# Control.net
KiCad netlist of a schematic drawn in Altium Designer
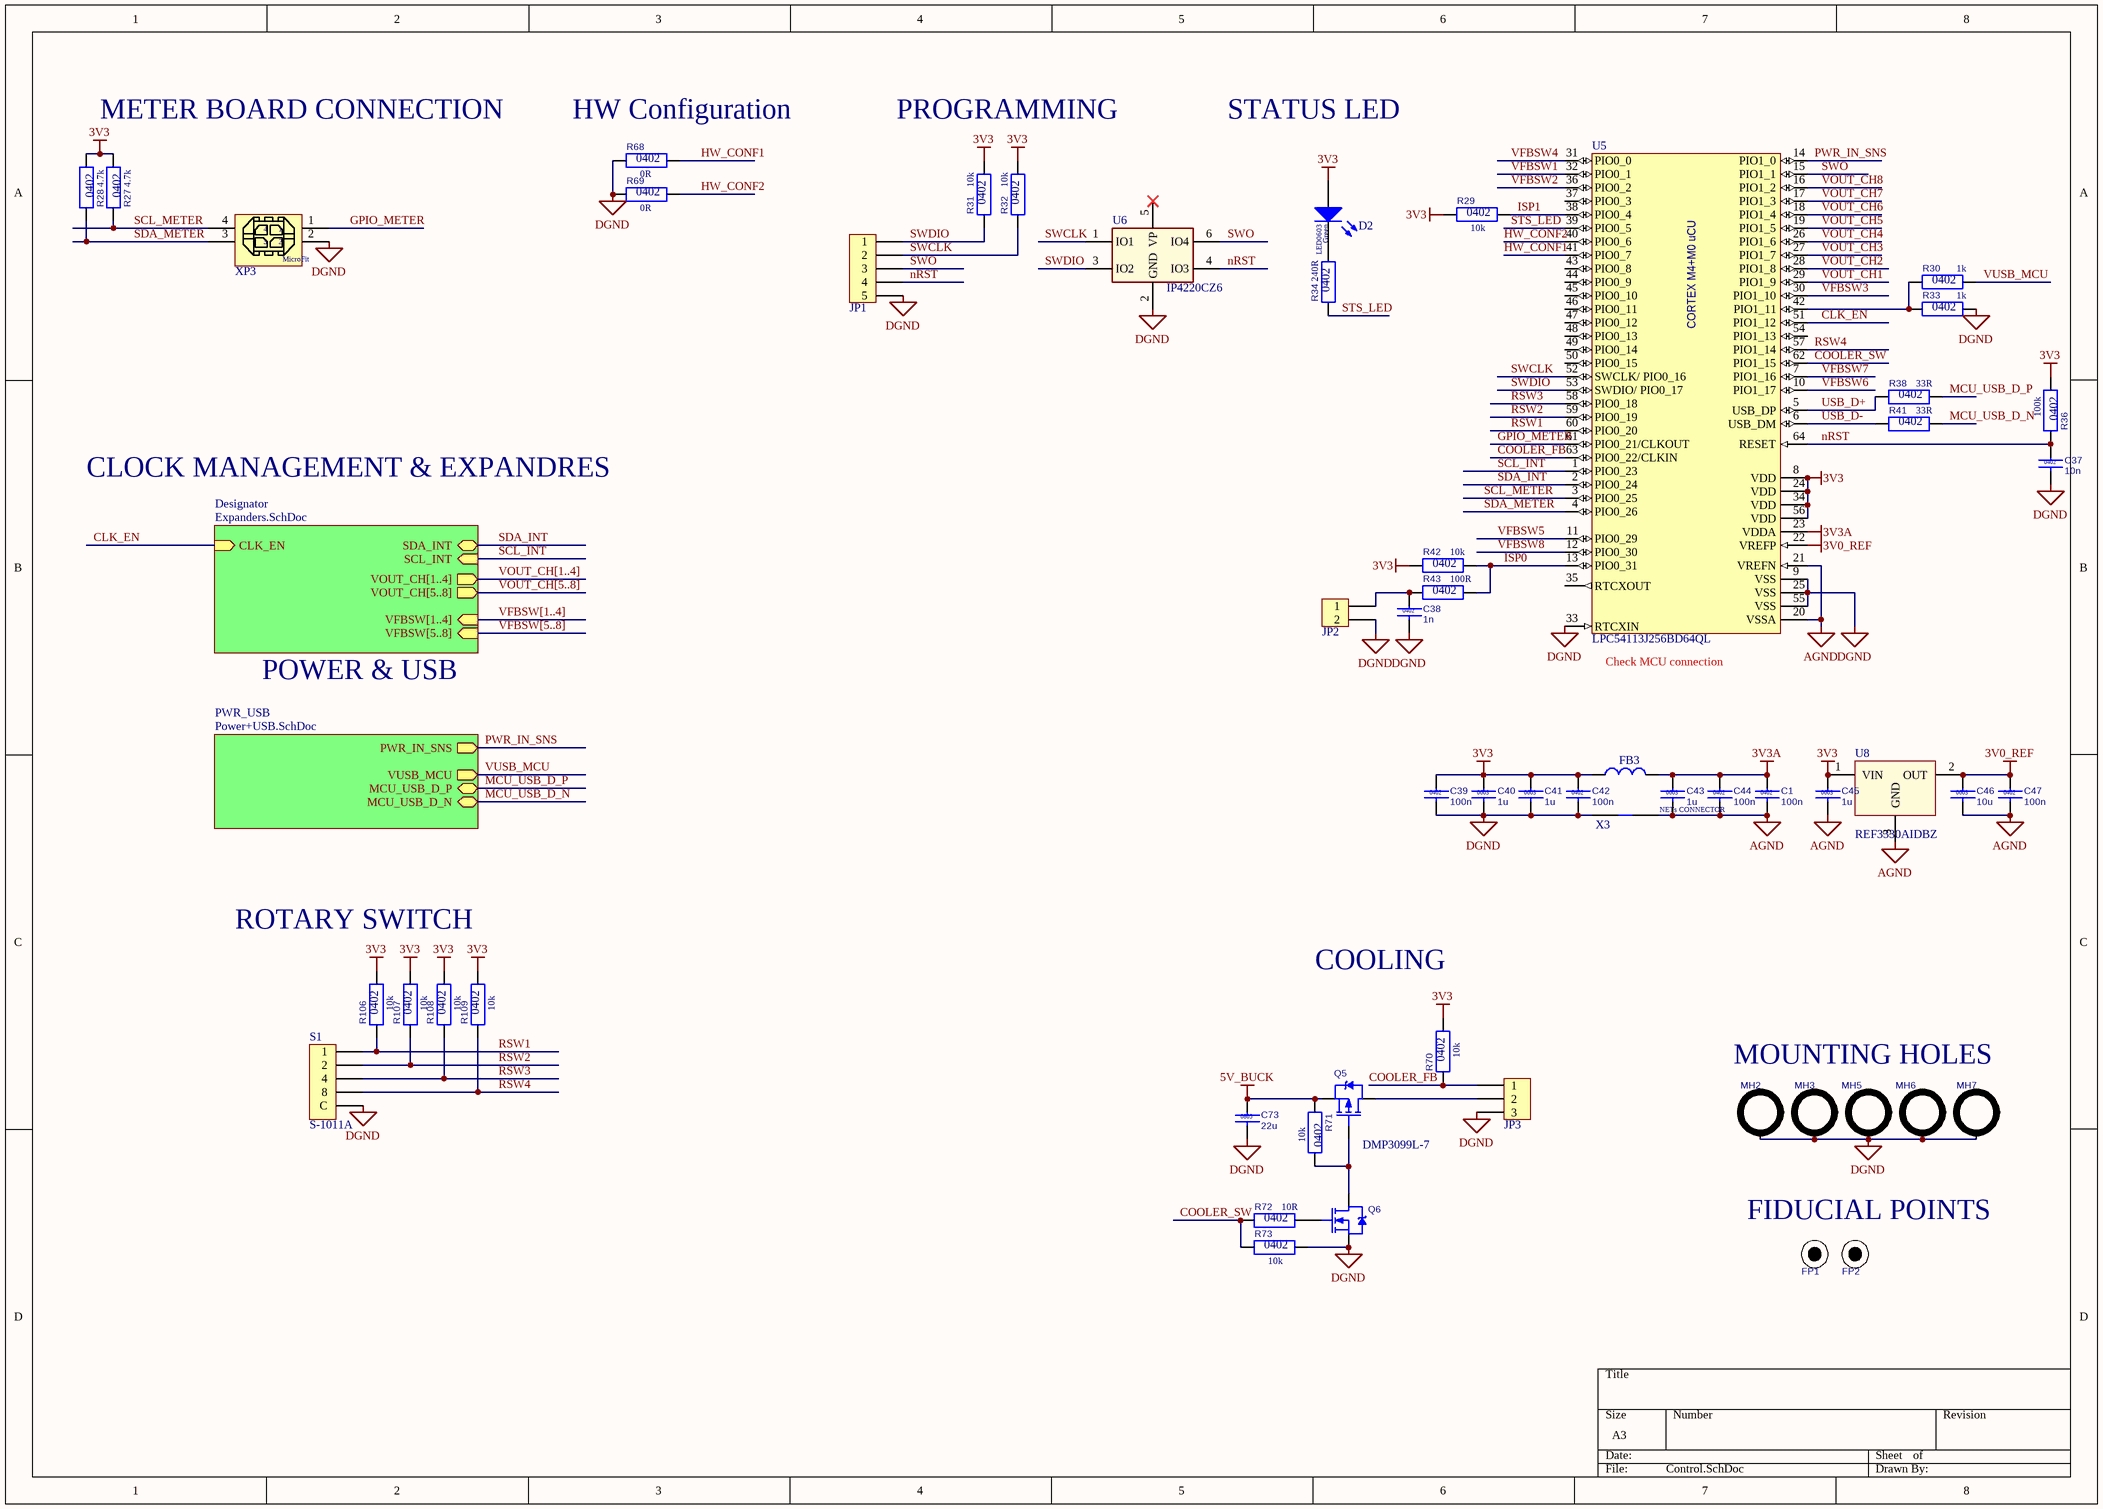
[diagram p0: Control.SchDoc]

(export (version "E")
  (design (tool "Eeschema 10.0.6"))
  (components
    (comp (ref "C1")
      (value "100n")
      (footprint "CC0402M")
      (description "Chip ceramic capacitor")
      (fields
        (field (name "CASE") "0402")
        (field (name "PARTNUMBER") "CC0402K-X7R-25V-100N-M")
        (field (name "MANUFACTURER") "Murata")
        (field (name "PUBLISHER") "alexey.savchenko")
      )
      (libsource (lib "AltiumLib") (part "Capacitor_nonpolar"))
    )
    (comp (ref "C37")
      (value "10n")
      (footprint "CC0402M")
      (description "Chip ceramic capacitor")
      (fields
        (field (name "CASE") "0402")
        (field (name "PARTNUMBER") "CC0402K-X7R-50V-10N-M")
        (field (name "MANUFACTURER") "Yageo")
        (field (name "PUBLISHER") "alexey.savchenko")
      )
      (libsource (lib "AltiumLib") (part "Capacitor_nonpolar"))
    )
    (comp (ref "C38")
      (value "1n")
      (footprint "CC0402M")
      (description "Chip ceramic capacitor")
      (fields
        (field (name "CASE") "0402")
        (field (name "PARTNUMBER") "CC0402K-X7R-50V-1N-M")
        (field (name "MANUFACTURER") "Yageo")
        (field (name "PUBLISHER") "alexey.savchenko")
      )
      (libsource (lib "AltiumLib") (part "Capacitor_nonpolar"))
    )
    (comp (ref "C39")
      (value "100n")
      (footprint "CC0402M")
      (description "Chip ceramic capacitor")
      (fields
        (field (name "CASE") "0402")
        (field (name "PARTNUMBER") "CC0402K-X7R-25V-100N-M")
        (field (name "MANUFACTURER") "Murata")
        (field (name "PUBLISHER") "alexey.savchenko")
      )
      (libsource (lib "AltiumLib") (part "Capacitor_nonpolar"))
    )
    (comp (ref "C40")
      (value "1u")
      (footprint "CC0603M")
      (description "Chip ceramic capacitor")
      (fields
        (field (name "CASE") "0603")
        (field (name "PARTNUMBER") "CC0603K-X7R-10V-1U-M")
        (field (name "MANUFACTURER") "Samsung")
        (field (name "PUBLISHER") "alexey.savchenko")
      )
      (libsource (lib "AltiumLib") (part "Capacitor_nonpolar"))
    )
    (comp (ref "C41")
      (value "1u")
      (footprint "CC0603M")
      (description "Chip ceramic capacitor")
      (fields
        (field (name "CASE") "0603")
        (field (name "PARTNUMBER") "CC0603K-X7R-10V-1U-M")
        (field (name "MANUFACTURER") "Samsung")
        (field (name "PUBLISHER") "alexey.savchenko")
      )
      (libsource (lib "AltiumLib") (part "Capacitor_nonpolar"))
    )
    (comp (ref "C42")
      (value "100n")
      (footprint "CC0402M")
      (description "Chip ceramic capacitor")
      (fields
        (field (name "CASE") "0402")
        (field (name "PARTNUMBER") "CC0402K-X7R-25V-100N-M")
        (field (name "MANUFACTURER") "Murata")
        (field (name "PUBLISHER") "alexey.savchenko")
      )
      (libsource (lib "AltiumLib") (part "Capacitor_nonpolar"))
    )
    (comp (ref "C43")
      (value "1u")
      (footprint "CC0603M")
      (description "Chip ceramic capacitor")
      (fields
        (field (name "CASE") "0603")
        (field (name "PARTNUMBER") "CC0603K-X7R-10V-1U-M")
        (field (name "MANUFACTURER") "Samsung")
        (field (name "PUBLISHER") "alexey.savchenko")
      )
      (libsource (lib "AltiumLib") (part "Capacitor_nonpolar"))
    )
    (comp (ref "C44")
      (value "100n")
      (footprint "CC0402M")
      (description "Chip ceramic capacitor")
      (fields
        (field (name "CASE") "0402")
        (field (name "PARTNUMBER") "CC0402K-X7R-25V-100N-M")
        (field (name "MANUFACTURER") "Murata")
        (field (name "PUBLISHER") "alexey.savchenko")
      )
      (libsource (lib "AltiumLib") (part "Capacitor_nonpolar"))
    )
    (comp (ref "C45")
      (value "1u")
      (footprint "CC0603M")
      (description "Chip ceramic capacitor")
      (fields
        (field (name "CASE") "0603")
        (field (name "PARTNUMBER") "CC0603K-X7R-10V-1U-M")
        (field (name "MANUFACTURER") "Samsung")
        (field (name "PUBLISHER") "alexey.savchenko")
      )
      (libsource (lib "AltiumLib") (part "Capacitor_nonpolar"))
    )
    (comp (ref "C46")
      (value "10u")
      (footprint "CC0603M")
      (description "Chip ceramic capacitor")
      (fields
        (field (name "CASE") "0603")
        (field (name "PARTNUMBER") "CC0603K-X5R-10V-10U-M")
        (field (name "MANUFACTURER") "Murata")
        (field (name "PUBLISHER") "alexey.savchenko")
      )
      (libsource (lib "AltiumLib") (part "Capacitor_nonpolar"))
    )
    (comp (ref "C47")
      (value "100n")
      (footprint "CC0402M")
      (description "Chip ceramic capacitor")
      (fields
        (field (name "CASE") "0402")
        (field (name "PARTNUMBER") "CC0402K-X7R-25V-100N-M")
        (field (name "MANUFACTURER") "Murata")
        (field (name "PUBLISHER") "alexey.savchenko")
      )
      (libsource (lib "AltiumLib") (part "Capacitor_nonpolar"))
    )
    (comp (ref "C73")
      (value "22u")
      (footprint "CC0805M")
      (description "Chip ceramic capacitor")
      (fields
        (field (name "CASE") "0805")
        (field (name "PARTNUMBER") "CC0805K-X5R-10V-22U-M")
        (field (name "MANUFACTURER") "Samsung")
        (field (name "PUBLISHER") "alexey.savchenko")
      )
      (libsource (lib "AltiumLib") (part "Capacitor_nonpolar"))
    )
    (comp (ref "D2")
      (value "150060GS75000")
      (footprint "LED0603")
      (description "LED GREEN CLEAR 0603 SMD")
      (fields
        (field (name "CASE") "LED0603")
        (field (name "COLOR") "Green")
        (field (name "MANUFACTURER") "Würth Elektronik")
        (field (name "PUBLISHER") "alexey.savchenko")
      )
      (libsource (lib "AltiumLib") (part "LED"))
    )
    (comp (ref "FB3")
      (value "BLM18HG102SN1D")
      (footprint "FB0603M")
      (description "FERRITE BEAD 1 KOHM 0603 1LN")
      (fields (field (name "MANUFACTURER") "Murata") (field (name "PUBLISHER") "alexey.savchenko"))
      (libsource (lib "AltiumLib") (part "FerriteBead"))
    )
    (comp (ref "FP1")
      (value "FP")
      (footprint "FP")
      (description "No BOM component to short circuit 2 nets")
      (fields (field (name "MANUFACTURER") "NULL") (field (name "PUBLISHER") "alexey.savchenko"))
      (libsource (lib "AltiumLib") (part "FP"))
    )
    (comp (ref "FP2")
      (value "FP")
      (footprint "FP")
      (description "No BOM component to short circuit 2 nets")
      (fields (field (name "MANUFACTURER") "NULL") (field (name "PUBLISHER") "alexey.savchenko"))
      (libsource (lib "AltiumLib") (part "FP"))
    )
    (comp (ref "JP1")
      (value "HEADER-2.54-THR-1x5-MV")
      (footprint "HEADER-2.54-THR-1x5-MV")
      (description "Header Connector, 2.54mm pitch, Single, 5 contacts, Male, Vertical")
      (fields (field (name "MANUFACTURER") "Adam Tech") (field (name "PUBLISHER") "alexey.savchenko"))
      (libsource (lib "AltiumLib") (part "HEADER-1x5"))
    )
    (comp (ref "JP2")
      (value "HEADER-2.54-THR-1x2-MV")
      (footprint "HEADER-2.54-THR-1x2-MV")
      (description "Header Connector, 2.54mm pitch, Single, 2 contacts, Male, Vertical")
      (fields (field (name "MANUFACTURER") "Adam Tech") (field (name "PUBLISHER") "alexey.savchenko"))
      (libsource (lib "AltiumLib") (part "HEADER-1x2"))
    )
    (comp (ref "JP3")
      (value "HEADER-2.54-THR-1x3-MV")
      (footprint "HEADER-2.54-THR-1x3-MV")
      (description "Header Connector, 2.54mm pitch, Single, 3 contacts, Male, Vertical")
      (fields (field (name "MANUFACTURER") "Adam Tech") (field (name "PUBLISHER") "alexey.savchenko"))
      (libsource (lib "AltiumLib") (part "HEADER-1x3"))
    )
    (comp (ref "MH2")
      (value "MH-3.5-PLATED")
      (footprint "MH_3.5_PLATED")
      (description "Mounting Hole")
      (fields (field (name "MANUFACTURER") "NULL") (field (name "PUBLISHER") "alexey.savchenko"))
      (libsource (lib "AltiumLib") (part "MH_MISC"))
    )
    (comp (ref "MH3")
      (value "MH-3.5-PLATED")
      (footprint "MH_3.5_PLATED")
      (description "Mounting Hole")
      (fields (field (name "MANUFACTURER") "NULL") (field (name "PUBLISHER") "alexey.savchenko"))
      (libsource (lib "AltiumLib") (part "MH_MISC"))
    )
    (comp (ref "MH5")
      (value "MH-3.5-PLATED")
      (footprint "MH_3.5_PLATED")
      (description "Mounting Hole")
      (fields (field (name "MANUFACTURER") "NULL") (field (name "PUBLISHER") "alexey.savchenko"))
      (libsource (lib "AltiumLib") (part "MH_MISC"))
    )
    (comp (ref "MH6")
      (value "MH-3.5-PLATED")
      (footprint "MH_3.5_PLATED")
      (description "Mounting Hole")
      (fields (field (name "MANUFACTURER") "NULL") (field (name "PUBLISHER") "alexey.savchenko"))
      (libsource (lib "AltiumLib") (part "MH_MISC"))
    )
    (comp (ref "MH7")
      (value "MH-3.5-PLATED")
      (footprint "MH_3.5_PLATED")
      (description "Mounting Hole")
      (fields (field (name "MANUFACTURER") "NULL") (field (name "PUBLISHER") "alexey.savchenko"))
      (libsource (lib "AltiumLib") (part "MH_MISC"))
    )
    (comp (ref "Q5")
      (value "DMP3099L-7")
      (footprint "SOT23-3")
      (description "P-Channel 30V 3.8A (Ta) 1.08W (Ta) Surface Mount SOT-23")
      (fields (field (name "MANUFACTURER") "Diodes") (field (name "PUBLISHER") "alexey.savchenko"))
      (libsource (lib "AltiumLib") (part "MOSFET_P-CH"))
    )
    (comp (ref "Q6")
      (value "NX3020NAKW,115")
      (footprint "SOT323")
      (description "MOSFET N-CH 30V 180MA SOT323")
      (fields (field (name "MANUFACTURER") "Nexperia") (field (name "PUBLISHER") "alexey.savchenko"))
      (libsource (lib "AltiumLib") (part "MOSFET_N-CH"))
    )
    (comp (ref "R27")
      (value "4.7k")
      (footprint "RC0402M")
      (description "Chip resistor")
      (fields
        (field (name "CASE") "0402")
        (field (name "PARTNUMBER") "RC0402F-4K7-M")
        (field (name "POWER") "0.063W")
        (field (name "PUBLISHER") "alexey.savchenko")
      )
      (libsource (lib "AltiumLib") (part "Resistor"))
    )
    (comp (ref "R28")
      (value "4.7k")
      (footprint "RC0402M")
      (description "Chip resistor")
      (fields
        (field (name "CASE") "0402")
        (field (name "PARTNUMBER") "RC0402F-4K7-M")
        (field (name "POWER") "0.063W")
        (field (name "PUBLISHER") "alexey.savchenko")
      )
      (libsource (lib "AltiumLib") (part "Resistor"))
    )
    (comp (ref "R29")
      (value "10k")
      (footprint "RC0402M")
      (description "Chip resistor")
      (fields
        (field (name "CASE") "0402")
        (field (name "PARTNUMBER") "RC0402F-10K-M")
        (field (name "POWER") "0.063W")
        (field (name "PUBLISHER") "alexey.savchenko")
      )
      (libsource (lib "AltiumLib") (part "Resistor"))
    )
    (comp (ref "R30")
      (value "1k")
      (footprint "RC0402M")
      (description "Chip resistor")
      (fields
        (field (name "CASE") "0402")
        (field (name "PARTNUMBER") "RC0402F-1K-M")
        (field (name "POWER") "0.063W")
        (field (name "PUBLISHER") "alexey.savchenko")
      )
      (libsource (lib "AltiumLib") (part "Resistor"))
    )
    (comp (ref "R31")
      (value "10k")
      (footprint "RC0402M")
      (description "Chip resistor")
      (fields
        (field (name "CASE") "0402")
        (field (name "PARTNUMBER") "RC0402F-10K-M")
        (field (name "POWER") "0.063W")
        (field (name "PUBLISHER") "alexey.savchenko")
      )
      (libsource (lib "AltiumLib") (part "Resistor"))
    )
    (comp (ref "R32")
      (value "10k")
      (footprint "RC0402M")
      (description "Chip resistor")
      (fields
        (field (name "CASE") "0402")
        (field (name "PARTNUMBER") "RC0402F-10K-M")
        (field (name "POWER") "0.063W")
        (field (name "PUBLISHER") "alexey.savchenko")
      )
      (libsource (lib "AltiumLib") (part "Resistor"))
    )
    (comp (ref "R33")
      (value "1k")
      (footprint "RC0402M")
      (description "Chip resistor")
      (fields
        (field (name "CASE") "0402")
        (field (name "PARTNUMBER") "RC0402F-1K-M")
        (field (name "POWER") "0.063W")
        (field (name "PUBLISHER") "alexey.savchenko")
      )
      (libsource (lib "AltiumLib") (part "Resistor"))
    )
    (comp (ref "R34")
      (value "240R")
      (footprint "RC0402M")
      (description "Chip resistor")
      (fields
        (field (name "CASE") "0402")
        (field (name "PARTNUMBER") "RC0402F-240R-M")
        (field (name "POWER") "0.063W")
        (field (name "PUBLISHER") "alexey.savchenko")
      )
      (libsource (lib "AltiumLib") (part "Resistor"))
    )
    (comp (ref "R36")
      (value "100k")
      (footprint "RC0402M")
      (description "Chip resistor")
      (fields
        (field (name "CASE") "0402")
        (field (name "PARTNUMBER") "RC0402F-100K-M")
        (field (name "POWER") "0.063W")
        (field (name "PUBLISHER") "alexey.savchenko")
      )
      (libsource (lib "AltiumLib") (part "Resistor"))
    )
    (comp (ref "R38")
      (value "33R")
      (footprint "RC0402M")
      (description "Chip resistor")
      (fields
        (field (name "CASE") "0402")
        (field (name "PARTNUMBER") "RC0402F-33R-M")
        (field (name "POWER") "0.063W")
        (field (name "PUBLISHER") "alexey.savchenko")
      )
      (libsource (lib "AltiumLib") (part "Resistor"))
    )
    (comp (ref "R41")
      (value "33R")
      (footprint "RC0402M")
      (description "Chip resistor")
      (fields
        (field (name "CASE") "0402")
        (field (name "PARTNUMBER") "RC0402F-33R-M")
        (field (name "POWER") "0.063W")
        (field (name "PUBLISHER") "alexey.savchenko")
      )
      (libsource (lib "AltiumLib") (part "Resistor"))
    )
    (comp (ref "R42")
      (value "10k")
      (footprint "RC0402M")
      (description "Chip resistor")
      (fields
        (field (name "CASE") "0402")
        (field (name "PARTNUMBER") "RC0402F-10K-M")
        (field (name "POWER") "0.063W")
        (field (name "PUBLISHER") "alexey.savchenko")
      )
      (libsource (lib "AltiumLib") (part "Resistor"))
    )
    (comp (ref "R43")
      (value "100R")
      (footprint "RC0402M")
      (description "Chip resistor")
      (fields
        (field (name "CASE") "0402")
        (field (name "PARTNUMBER") "RC0402F-100R-M")
        (field (name "POWER") "0.063W")
        (field (name "PUBLISHER") "alexey.savchenko")
      )
      (libsource (lib "AltiumLib") (part "Resistor"))
    )
    (comp (ref "R68")
      (value "0R")
      (footprint "RC0402M")
      (description "Chip resistor")
      (fields
        (field (name "CASE") "0402")
        (field (name "PARTNUMBER") "RC0402F-0R-M")
        (field (name "MANUFACTURER") "Yageo")
        (field (name "PUBLISHER") "alexey.savchenko")
      )
      (libsource (lib "AltiumLib") (part "Resistor"))
    )
    (comp (ref "R69")
      (value "0R")
      (footprint "RC0402M")
      (description "Chip resistor")
      (fields
        (field (name "CASE") "0402")
        (field (name "PARTNUMBER") "RC0402F-0R-M")
        (field (name "MANUFACTURER") "Yageo")
        (field (name "PUBLISHER") "alexey.savchenko")
      )
      (libsource (lib "AltiumLib") (part "Resistor"))
    )
    (comp (ref "R70")
      (value "10k")
      (footprint "RC0402M")
      (description "Chip resistor")
      (fields
        (field (name "CASE") "0402")
        (field (name "PARTNUMBER") "RC0402F-10K-M")
        (field (name "MANUFACTURER") "Yageo")
        (field (name "PUBLISHER") "alexey.savchenko")
      )
      (libsource (lib "AltiumLib") (part "Resistor"))
    )
    (comp (ref "R71")
      (value "10k")
      (footprint "RC0402M")
      (description "Chip resistor")
      (fields
        (field (name "CASE") "0402")
        (field (name "PARTNUMBER") "RC0402F-10K-M")
        (field (name "MANUFACTURER") "Yageo")
        (field (name "PUBLISHER") "alexey.savchenko")
      )
      (libsource (lib "AltiumLib") (part "Resistor"))
    )
    (comp (ref "R72")
      (value "10R")
      (footprint "RC0402M")
      (description "Chip resistor")
      (fields
        (field (name "CASE") "0402")
        (field (name "PARTNUMBER") "RC0402F-10R-M")
        (field (name "MANUFACTURER") "Yageo")
        (field (name "PUBLISHER") "alexey.savchenko")
      )
      (libsource (lib "AltiumLib") (part "Resistor"))
    )
    (comp (ref "R73")
      (value "10k")
      (footprint "RC0402M")
      (description "Chip resistor")
      (fields
        (field (name "CASE") "0402")
        (field (name "PARTNUMBER") "RC0402F-10K-M")
        (field (name "MANUFACTURER") "Yageo")
        (field (name "PUBLISHER") "alexey.savchenko")
      )
      (libsource (lib "AltiumLib") (part "Resistor"))
    )
    (comp (ref "R106")
      (value "10k")
      (footprint "RC0402M")
      (description "Chip resistor")
      (fields
        (field (name "CASE") "0402")
        (field (name "PARTNUMBER") "RC0402F-10K-M")
        (field (name "MANUFACTURER") "Yageo")
        (field (name "PUBLISHER") "alexey.savchenko")
      )
      (libsource (lib "AltiumLib") (part "Resistor"))
    )
    (comp (ref "R107")
      (value "10k")
      (footprint "RC0402M")
      (description "Chip resistor")
      (fields
        (field (name "CASE") "0402")
        (field (name "PARTNUMBER") "RC0402F-10K-M")
        (field (name "MANUFACTURER") "Yageo")
        (field (name "PUBLISHER") "alexey.savchenko")
      )
      (libsource (lib "AltiumLib") (part "Resistor"))
    )
    (comp (ref "R108")
      (value "10k")
      (footprint "RC0402M")
      (description "Chip resistor")
      (fields
        (field (name "CASE") "0402")
        (field (name "PARTNUMBER") "RC0402F-10K-M")
        (field (name "MANUFACTURER") "Yageo")
        (field (name "PUBLISHER") "alexey.savchenko")
      )
      (libsource (lib "AltiumLib") (part "Resistor"))
    )
    (comp (ref "R109")
      (value "10k")
      (footprint "RC0402M")
      (description "Chip resistor")
      (fields
        (field (name "CASE") "0402")
        (field (name "PARTNUMBER") "RC0402F-10K-M")
        (field (name "MANUFACTURER") "Yageo")
        (field (name "PUBLISHER") "alexey.savchenko")
      )
      (libsource (lib "AltiumLib") (part "Resistor"))
    )
    (comp (ref "S1")
      (value "S-1011A")
      (footprint "S-1011A")
      (description "Dip Switch Hexadecimal 16 Position Through Hole, Right Angle Rotary for Tool Actuator 100mA 5VDC")
      (fields
        (field (name "MANUFACTURER") "Nidec Copal Electronics")
        (field (name "PUBLISHER") "alexey.savchenko")
      )
      (libsource (lib "AltiumLib") (part "S-1011A"))
    )
    (comp (ref "U5")
      (value "LPC54113J256BD64QL")
      (footprint "LQFP-64")
      (description "IC MCU 32BIT 256KB FLASH 64LQFP")
      (fields (field (name "MANUFACTURER") "NXP") (field (name "PUBLISHER") "alexey.savchenko"))
      (libsource (lib "AltiumLib") (part "LPC54113J256BD64QL"))
    )
    (comp (ref "U6")
      (value "IP4220CZ6")
      (footprint "TSOP-6")
      (description "TVS DIODE 5.5V 6TSOP")
      (fields (field (name "MANUFACTURER") "Nexperia") (field (name "PUBLISHER") "alexey.savchenko"))
      (libsource (lib "AltiumLib") (part "IP4220CZ6"))
    )
    (comp (ref "U8")
      (value "REF3330AIDBZ")
      (footprint "SOT23-3")
      (description "IC VREF SERIES 0.15% SOT23-3")
      (fields (field (name "MANUFACTURER") "TI") (field (name "PUBLISHER") "alexey.savchenko"))
      (libsource (lib "AltiumLib") (part "REF3330AIDBZ"))
    )
    (comp (ref "X3")
      (value "NETs_CONNECTOR")
      (footprint "NETs_CONNECTOR")
      (description "No BOM component to short circuit 2 nets")
      (fields (field (name "MANUFACTURER") "NULL") (field (name "PUBLISHER") "alexey.savchenko"))
      (libsource (lib "AltiumLib") (part "NETs_CONNECTOR"))
    )
    (comp (ref "XP3")
      (value "0447690401")
      (footprint "0447690401")
      (fields (field (name "MANUFACTURER") "Molex") (field (name "PUBLISHER") "alexey.savchenko"))
      (libsource (lib "AltiumLib") (part "MicroFit-2x2"))
    )
  )
  (nets
    (net (code "1") (name "/CLK_EN") (class "Default")
      (node (ref "U5") (pin "51") (pinfunction "PIO1_12_51") (pintype "bidirectional"))
    )
    (net (code "2") (name "/COOLER_FB") (class "Default")
      (node (ref "JP3") (pin "1") (pinfunction "1_1") (pintype "passive"))
      (node (ref "R70") (pin "1") (pinfunction "1_1") (pintype "passive"))
      (node (ref "U5") (pin "63") (pinfunction "PIO0_22/CLKIN_63") (pintype "bidirectional"))
    )
    (net (code "3") (name "/COOLER_SW") (class "Default")
      (node (ref "R72") (pin "1") (pinfunction "1_1") (pintype "passive"))
      (node (ref "R73") (pin "1") (pinfunction "1_1") (pintype "passive"))
      (node (ref "U5") (pin "62") (pinfunction "PIO1_15_62") (pintype "bidirectional"))
    )
    (net (code "4") (name "/GPIO_METER") (class "Default")
      (node (ref "U5") (pin "61") (pinfunction "PIO0_21/CLKOUT_61") (pintype "bidirectional"))
      (node (ref "XP3") (pin "1") (pinfunction "1_1") (pintype "passive"))
    )
    (net (code "5") (name "/HW_CONF1") (class "Default")
      (node (ref "R68") (pin "2") (pinfunction "2_2") (pintype "passive"))
      (node (ref "U5") (pin "41") (pinfunction "PIO0_7_41") (pintype "bidirectional"))
    )
    (net (code "6") (name "/HW_CONF2") (class "Default")
      (node (ref "R69") (pin "2") (pinfunction "2_2") (pintype "passive"))
      (node (ref "U5") (pin "40") (pinfunction "PIO0_6_40") (pintype "bidirectional"))
    )
    (net (code "7") (name "/ISP0") (class "Default")
      (node (ref "R42") (pin "2") (pinfunction "2_2") (pintype "passive"))
      (node (ref "R43") (pin "2") (pinfunction "2_2") (pintype "passive"))
      (node (ref "U5") (pin "13") (pinfunction "PIO0_31_13") (pintype "bidirectional"))
    )
    (net (code "8") (name "/ISP1") (class "Default")
      (node (ref "R29") (pin "2") (pinfunction "2_2") (pintype "passive"))
      (node (ref "U5") (pin "38") (pinfunction "PIO0_4_38") (pintype "bidirectional"))
    )
    (net (code "9") (name "/MCU_USB_D_N") (class "Default")
      (node (ref "R41") (pin "2") (pinfunction "2_2") (pintype "passive"))
    )
    (net (code "10") (name "/MCU_USB_D_P") (class "Default")
      (node (ref "R38") (pin "2") (pinfunction "2_2") (pintype "passive"))
    )
    (net (code "11") (name "/PWR_IN_SNS") (class "Default")
      (node (ref "U5") (pin "14") (pinfunction "PIO1_0_14") (pintype "bidirectional"))
    )
    (net (code "12") (name "/RSW1") (class "Default")
      (node (ref "R106") (pin "1") (pinfunction "1_1") (pintype "passive"))
      (node (ref "S1") (pin "1") (pinfunction "1_1") (pintype "passive"))
      (node (ref "U5") (pin "60") (pinfunction "PIO0_20_60") (pintype "bidirectional"))
    )
    (net (code "13") (name "/RSW2") (class "Default")
      (node (ref "R107") (pin "1") (pinfunction "1_1") (pintype "passive"))
      (node (ref "S1") (pin "2") (pinfunction "2_2") (pintype "passive"))
      (node (ref "U5") (pin "59") (pinfunction "PIO0_19_59") (pintype "bidirectional"))
    )
    (net (code "14") (name "/RSW3") (class "Default")
      (node (ref "R108") (pin "1") (pinfunction "1_1") (pintype "passive"))
      (node (ref "S1") (pin "4") (pinfunction "4_4") (pintype "passive"))
      (node (ref "U5") (pin "58") (pinfunction "PIO0_18_58") (pintype "bidirectional"))
    )
    (net (code "15") (name "/RSW4") (class "Default")
      (node (ref "R109") (pin "1") (pinfunction "1_1") (pintype "passive"))
      (node (ref "S1") (pin "8") (pinfunction "8_8") (pintype "passive"))
      (node (ref "U5") (pin "57") (pinfunction "PIO1_14_57") (pintype "bidirectional"))
    )
    (net (code "16") (name "/SCL_INT") (class "Default")
      (node (ref "U5") (pin "1") (pinfunction "PIO0_23_1") (pintype "bidirectional"))
    )
    (net (code "17") (name "/SCL_METER") (class "Default")
      (node (ref "R27") (pin "1") (pinfunction "1_1") (pintype "passive"))
      (node (ref "U5") (pin "3") (pinfunction "PIO0_25_3") (pintype "bidirectional"))
      (node (ref "XP3") (pin "4") (pinfunction "4_4") (pintype "passive"))
    )
    (net (code "18") (name "/SDA_INT") (class "Default")
      (node (ref "U5") (pin "2") (pinfunction "PIO0_24_2") (pintype "bidirectional"))
    )
    (net (code "19") (name "/SDA_METER") (class "Default")
      (node (ref "R28") (pin "1") (pinfunction "1_1") (pintype "passive"))
      (node (ref "U5") (pin "4") (pinfunction "PIO0_26_4") (pintype "bidirectional"))
      (node (ref "XP3") (pin "3") (pinfunction "3_3") (pintype "passive"))
    )
    (net (code "20") (name "/STS_LED") (class "Default")
      (node (ref "R34") (pin "1") (pinfunction "1_1") (pintype "passive"))
      (node (ref "U5") (pin "39") (pinfunction "PIO0_5_39") (pintype "bidirectional"))
    )
    (net (code "21") (name "/SWCLK") (class "Default")
      (node (ref "JP1") (pin "2") (pinfunction "2_2") (pintype "passive"))
      (node (ref "R32") (pin "1") (pinfunction "1_1") (pintype "passive"))
      (node (ref "U5") (pin "52") (pinfunction "SWCLK/_PIO0_16_52") (pintype "bidirectional"))
      (node (ref "U6") (pin "1") (pinfunction "IO1_1") (pintype "passive"))
    )
    (net (code "22") (name "/SWDIO") (class "Default")
      (node (ref "JP1") (pin "1") (pinfunction "1_1") (pintype "passive"))
      (node (ref "R31") (pin "1") (pinfunction "1_1") (pintype "passive"))
      (node (ref "U5") (pin "53") (pinfunction "SWDIO/_PIO0_17_53") (pintype "bidirectional"))
      (node (ref "U6") (pin "3") (pinfunction "IO2_3") (pintype "passive"))
    )
    (net (code "23") (name "/SWO") (class "Default")
      (node (ref "JP1") (pin "3") (pinfunction "3_3") (pintype "passive"))
      (node (ref "U5") (pin "15") (pinfunction "PIO1_1_15") (pintype "bidirectional"))
      (node (ref "U6") (pin "6") (pinfunction "IO4_6") (pintype "passive"))
    )
    (net (code "24") (name "/USB_D+") (class "Default")
      (node (ref "R38") (pin "1") (pinfunction "1_1") (pintype "passive"))
      (node (ref "U5") (pin "5") (pinfunction "USB_DP_5") (pintype "bidirectional"))
    )
    (net (code "25") (name "/USB_D-") (class "Default")
      (node (ref "R41") (pin "1") (pinfunction "1_1") (pintype "passive"))
      (node (ref "U5") (pin "6") (pinfunction "USB_DM_6") (pintype "bidirectional"))
    )
    (net (code "26") (name "/VFBSW1") (class "Default")
      (node (ref "U5") (pin "32") (pinfunction "PIO0_1_32") (pintype "bidirectional"))
    )
    (net (code "27") (name "/VFBSW2") (class "Default")
      (node (ref "U5") (pin "36") (pinfunction "PIO0_2_36") (pintype "bidirectional"))
    )
    (net (code "28") (name "/VFBSW3") (class "Default")
      (node (ref "U5") (pin "30") (pinfunction "PIO1_10_30") (pintype "bidirectional"))
    )
    (net (code "29") (name "/VFBSW4") (class "Default")
      (node (ref "U5") (pin "31") (pinfunction "PIO0_0_31") (pintype "bidirectional"))
    )
    (net (code "30") (name "/VFBSW5") (class "Default")
      (node (ref "U5") (pin "11") (pinfunction "PIO0_29_11") (pintype "bidirectional"))
    )
    (net (code "31") (name "/VFBSW6") (class "Default")
      (node (ref "U5") (pin "10") (pinfunction "PIO1_17_10") (pintype "bidirectional"))
    )
    (net (code "32") (name "/VFBSW7") (class "Default")
      (node (ref "U5") (pin "7") (pinfunction "PIO1_16_7") (pintype "bidirectional"))
    )
    (net (code "33") (name "/VFBSW8") (class "Default")
      (node (ref "U5") (pin "12") (pinfunction "PIO0_30_12") (pintype "bidirectional"))
    )
    (net (code "36") (name "/VOUT_CH1") (class "Default")
      (node (ref "U5") (pin "29") (pinfunction "PIO1_9_29") (pintype "bidirectional"))
    )
    (net (code "37") (name "/VOUT_CH2") (class "Default")
      (node (ref "U5") (pin "28") (pinfunction "PIO1_8_28") (pintype "bidirectional"))
    )
    (net (code "38") (name "/VOUT_CH3") (class "Default")
      (node (ref "U5") (pin "27") (pinfunction "PIO1_7_27") (pintype "bidirectional"))
    )
    (net (code "39") (name "/VOUT_CH4") (class "Default")
      (node (ref "U5") (pin "26") (pinfunction "PIO1_6_26") (pintype "bidirectional"))
    )
    (net (code "40") (name "/VOUT_CH5") (class "Default")
      (node (ref "U5") (pin "19") (pinfunction "PIO1_5_19") (pintype "bidirectional"))
    )
    (net (code "41") (name "/VOUT_CH6") (class "Default")
      (node (ref "U5") (pin "18") (pinfunction "PIO1_4_18") (pintype "bidirectional"))
    )
    (net (code "42") (name "/VOUT_CH7") (class "Default")
      (node (ref "U5") (pin "17") (pinfunction "PIO1_3_17") (pintype "bidirectional"))
    )
    (net (code "43") (name "/VOUT_CH8") (class "Default")
      (node (ref "U5") (pin "16") (pinfunction "PIO1_2_16") (pintype "bidirectional"))
    )
    (net (code "46") (name "/VUSB_MCU") (class "Default")
      (node (ref "R30") (pin "2") (pinfunction "2_2") (pintype "passive"))
    )
    (net (code "47") (name "/nRST") (class "Default")
      (node (ref "C37") (pin "1") (pinfunction "1_1") (pintype "passive"))
      (node (ref "JP1") (pin "4") (pinfunction "4_4") (pintype "passive"))
      (node (ref "R36") (pin "1") (pinfunction "1_1") (pintype "passive"))
      (node (ref "U5") (pin "64") (pinfunction "RESET_64") (pintype "input"))
      (node (ref "U6") (pin "4") (pinfunction "IO3_4") (pintype "passive"))
    )
    (net (code "48") (name "3V0_REF") (class "Default")
      (node (ref "C46") (pin "1") (pinfunction "1_1") (pintype "passive"))
      (node (ref "C47") (pin "1") (pinfunction "1_1") (pintype "passive"))
      (node (ref "U5") (pin "22") (pinfunction "VREFP_22") (pintype "input"))
      (node (ref "U8") (pin "2") (pinfunction "OUT_2") (pintype "passive"))
    )
    (net (code "49") (name "3V3") (class "Default")
      (node (ref "C39") (pin "1") (pinfunction "1_1") (pintype "passive"))
      (node (ref "C40") (pin "1") (pinfunction "1_1") (pintype "passive"))
      (node (ref "C41") (pin "1") (pinfunction "1_1") (pintype "passive"))
      (node (ref "C42") (pin "1") (pinfunction "1_1") (pintype "passive"))
      (node (ref "C45") (pin "1") (pinfunction "1_1") (pintype "passive"))
      (node (ref "D2") (pin "2") (pinfunction "A_2") (pintype "passive"))
      (node (ref "FB3") (pin "1") (pinfunction "1_1") (pintype "passive"))
      (node (ref "R106") (pin "2") (pinfunction "2_2") (pintype "passive"))
      (node (ref "R107") (pin "2") (pinfunction "2_2") (pintype "passive"))
      (node (ref "R108") (pin "2") (pinfunction "2_2") (pintype "passive"))
      (node (ref "R109") (pin "2") (pinfunction "2_2") (pintype "passive"))
      (node (ref "R27") (pin "2") (pinfunction "2_2") (pintype "passive"))
      (node (ref "R28") (pin "2") (pinfunction "2_2") (pintype "passive"))
      (node (ref "R29") (pin "1") (pinfunction "1_1") (pintype "passive"))
      (node (ref "R31") (pin "2") (pinfunction "2_2") (pintype "passive"))
      (node (ref "R32") (pin "2") (pinfunction "2_2") (pintype "passive"))
      (node (ref "R36") (pin "2") (pinfunction "2_2") (pintype "passive"))
      (node (ref "R42") (pin "1") (pinfunction "1_1") (pintype "passive"))
      (node (ref "R70") (pin "2") (pinfunction "2_2") (pintype "passive"))
      (node (ref "U5") (pin "24") (pinfunction "VDD_24") (pintype "power_in"))
      (node (ref "U5") (pin "34") (pinfunction "VDD_34") (pintype "power_in"))
      (node (ref "U5") (pin "56") (pinfunction "VDD_56") (pintype "power_in"))
      (node (ref "U5") (pin "8") (pinfunction "VDD_8") (pintype "power_in"))
      (node (ref "U8") (pin "1") (pinfunction "VIN_1") (pintype "passive"))
    )
    (net (code "50") (name "3V3A") (class "Default")
      (node (ref "C1") (pin "1") (pinfunction "1_1") (pintype "passive"))
      (node (ref "C43") (pin "1") (pinfunction "1_1") (pintype "passive"))
      (node (ref "C44") (pin "1") (pinfunction "1_1") (pintype "passive"))
      (node (ref "FB3") (pin "2") (pinfunction "2_2") (pintype "passive"))
      (node (ref "U5") (pin "23") (pinfunction "VDDA_23") (pintype "power_in"))
    )
    (net (code "51") (name "5V_BUCK") (class "Default")
      (node (ref "C73") (pin "1") (pinfunction "1_1") (pintype "passive"))
      (node (ref "Q5") (pin "2") (pinfunction "S_2") (pintype "passive"))
      (node (ref "R71") (pin "1") (pinfunction "1_1") (pintype "passive"))
    )
    (net (code "52") (name "AGND") (class "Default")
      (node (ref "C1") (pin "2") (pinfunction "2_2") (pintype "passive"))
      (node (ref "C43") (pin "2") (pinfunction "2_2") (pintype "passive"))
      (node (ref "C44") (pin "2") (pinfunction "2_2") (pintype "passive"))
      (node (ref "C45") (pin "2") (pinfunction "2_2") (pintype "passive"))
      (node (ref "C46") (pin "2") (pinfunction "2_2") (pintype "passive"))
      (node (ref "C47") (pin "2") (pinfunction "2_2") (pintype "passive"))
      (node (ref "U5") (pin "20") (pinfunction "VSSA_20") (pintype "power_in"))
      (node (ref "U5") (pin "21") (pinfunction "VREFN_21") (pintype "input"))
      (node (ref "U8") (pin "3") (pinfunction "GND_3") (pintype "passive"))
      (node (ref "X3") (pin "1") (pinfunction "1_1") (pintype "passive"))
    )
    (net (code "53") (name "DGND") (class "Default")
      (node (ref "C37") (pin "2") (pinfunction "2_2") (pintype "passive"))
      (node (ref "C38") (pin "2") (pinfunction "2_2") (pintype "passive"))
      (node (ref "C39") (pin "2") (pinfunction "2_2") (pintype "passive"))
      (node (ref "C40") (pin "2") (pinfunction "2_2") (pintype "passive"))
      (node (ref "C41") (pin "2") (pinfunction "2_2") (pintype "passive"))
      (node (ref "C42") (pin "2") (pinfunction "2_2") (pintype "passive"))
      (node (ref "C73") (pin "2") (pinfunction "2_2") (pintype "passive"))
      (node (ref "JP1") (pin "5") (pinfunction "5_5") (pintype "passive"))
      (node (ref "JP2") (pin "2") (pinfunction "2_2") (pintype "passive"))
      (node (ref "JP3") (pin "3") (pinfunction "3_3") (pintype "passive"))
      (node (ref "MH2") (pin "0") (pinfunction "0_0") (pintype "passive"))
      (node (ref "MH3") (pin "0") (pinfunction "0_0") (pintype "passive"))
      (node (ref "MH5") (pin "0") (pinfunction "0_0") (pintype "passive"))
      (node (ref "MH6") (pin "0") (pinfunction "0_0") (pintype "passive"))
      (node (ref "MH7") (pin "0") (pinfunction "0_0") (pintype "passive"))
      (node (ref "Q6") (pin "2") (pinfunction "S_2") (pintype "passive"))
      (node (ref "R33") (pin "2") (pinfunction "2_2") (pintype "passive"))
      (node (ref "R68") (pin "1") (pinfunction "1_1") (pintype "passive"))
      (node (ref "R69") (pin "1") (pinfunction "1_1") (pintype "passive"))
      (node (ref "R73") (pin "2") (pinfunction "2_2") (pintype "passive"))
      (node (ref "S1") (pin "C") (pinfunction "C_C") (pintype "passive"))
      (node (ref "U5") (pin "25") (pinfunction "VSS_25") (pintype "power_in"))
      (node (ref "U5") (pin "33") (pinfunction "RTCXIN_33") (pintype "input"))
      (node (ref "U5") (pin "55") (pinfunction "VSS_55") (pintype "power_in"))
      (node (ref "U5") (pin "9") (pinfunction "VSS_9") (pintype "power_in"))
      (node (ref "U6") (pin "2") (pinfunction "GND_2") (pintype "passive"))
      (node (ref "X3") (pin "2") (pinfunction "2_2") (pintype "passive"))
      (node (ref "XP3") (pin "2") (pinfunction "2_2") (pintype "passive"))
    )
    (net (code "54") (name "Net-(C38-Pad1)") (class "Default")
      (node (ref "C38") (pin "1") (pinfunction "1_1") (pintype "passive"))
      (node (ref "JP2") (pin "1") (pinfunction "1_1") (pintype "passive"))
      (node (ref "R43") (pin "1") (pinfunction "1_1") (pintype "passive"))
    )
    (net (code "55") (name "Net-(D2-K)") (class "Default")
      (node (ref "D2") (pin "1") (pinfunction "K_1") (pintype "passive"))
      (node (ref "R34") (pin "2") (pinfunction "2_2") (pintype "passive"))
    )
    (net (code "56") (name "Net-(Q5-D)") (class "Default")
      (node (ref "JP3") (pin "2") (pinfunction "2_2") (pintype "passive"))
      (node (ref "Q5") (pin "3") (pinfunction "D_3") (pintype "passive"))
    )
    (net (code "57") (name "Net-(Q5-G)") (class "Default")
      (node (ref "Q5") (pin "1") (pinfunction "G_1") (pintype "passive"))
      (node (ref "Q6") (pin "3") (pinfunction "D_3") (pintype "passive"))
      (node (ref "R71") (pin "2") (pinfunction "2_2") (pintype "passive"))
    )
    (net (code "58") (name "Net-(Q6-G)") (class "Default")
      (node (ref "Q6") (pin "1") (pinfunction "G_1") (pintype "passive"))
      (node (ref "R72") (pin "2") (pinfunction "2_2") (pintype "passive"))
    )
    (net (code "59") (name "Net-(U5-PIO1_11)") (class "Default")
      (node (ref "R30") (pin "1") (pinfunction "1_1") (pintype "passive"))
      (node (ref "R33") (pin "1") (pinfunction "1_1") (pintype "passive"))
      (node (ref "U5") (pin "42") (pinfunction "PIO1_11_42") (pintype "bidirectional"))
    )
    (net (code "60") (name "unconnected-(U5-PIO0_3-Pad37)") (class "Default")
      (node (ref "U5") (pin "37") (pinfunction "PIO0_3_37") (pintype "bidirectional"))
    )
    (net (code "61") (name "unconnected-(U5-PIO0_8-Pad43)") (class "Default")
      (node (ref "U5") (pin "43") (pinfunction "PIO0_8_43") (pintype "bidirectional"))
    )
    (net (code "62") (name "unconnected-(U5-PIO0_9-Pad44)") (class "Default")
      (node (ref "U5") (pin "44") (pinfunction "PIO0_9_44") (pintype "bidirectional"))
    )
    (net (code "63") (name "unconnected-(U5-PIO0_10-Pad45)") (class "Default")
      (node (ref "U5") (pin "45") (pinfunction "PIO0_10_45") (pintype "bidirectional"))
    )
    (net (code "64") (name "unconnected-(U5-PIO0_11-Pad46)") (class "Default")
      (node (ref "U5") (pin "46") (pinfunction "PIO0_11_46") (pintype "bidirectional"))
    )
    (net (code "65") (name "unconnected-(U5-PIO0_12-Pad47)") (class "Default")
      (node (ref "U5") (pin "47") (pinfunction "PIO0_12_47") (pintype "bidirectional"))
    )
    (net (code "66") (name "unconnected-(U5-PIO0_13-Pad48)") (class "Default")
      (node (ref "U5") (pin "48") (pinfunction "PIO0_13_48") (pintype "bidirectional"))
    )
    (net (code "67") (name "unconnected-(U5-PIO0_14-Pad49)") (class "Default")
      (node (ref "U5") (pin "49") (pinfunction "PIO0_14_49") (pintype "bidirectional"))
    )
    (net (code "68") (name "unconnected-(U5-PIO0_15-Pad50)") (class "Default")
      (node (ref "U5") (pin "50") (pinfunction "PIO0_15_50") (pintype "bidirectional"))
    )
    (net (code "69") (name "unconnected-(U5-PIO1_13-Pad54)") (class "Default")
      (node (ref "U5") (pin "54") (pinfunction "PIO1_13_54") (pintype "bidirectional"))
    )
    (net (code "70") (name "unconnected-(U5-RTCXOUT-Pad35)") (class "Default")
      (node (ref "U5") (pin "35") (pinfunction "RTCXOUT_35") (pintype "output"))
    )
    (net (code "71") (name "unconnected-(U6-VP-Pad5)") (class "Default")
      (node (ref "U6") (pin "5") (pinfunction "VP_5") (pintype "passive+no_connect"))
    )
  )
)
